# clock-matrix.net
KiCad netlist of a schematic drawn in EAGLE
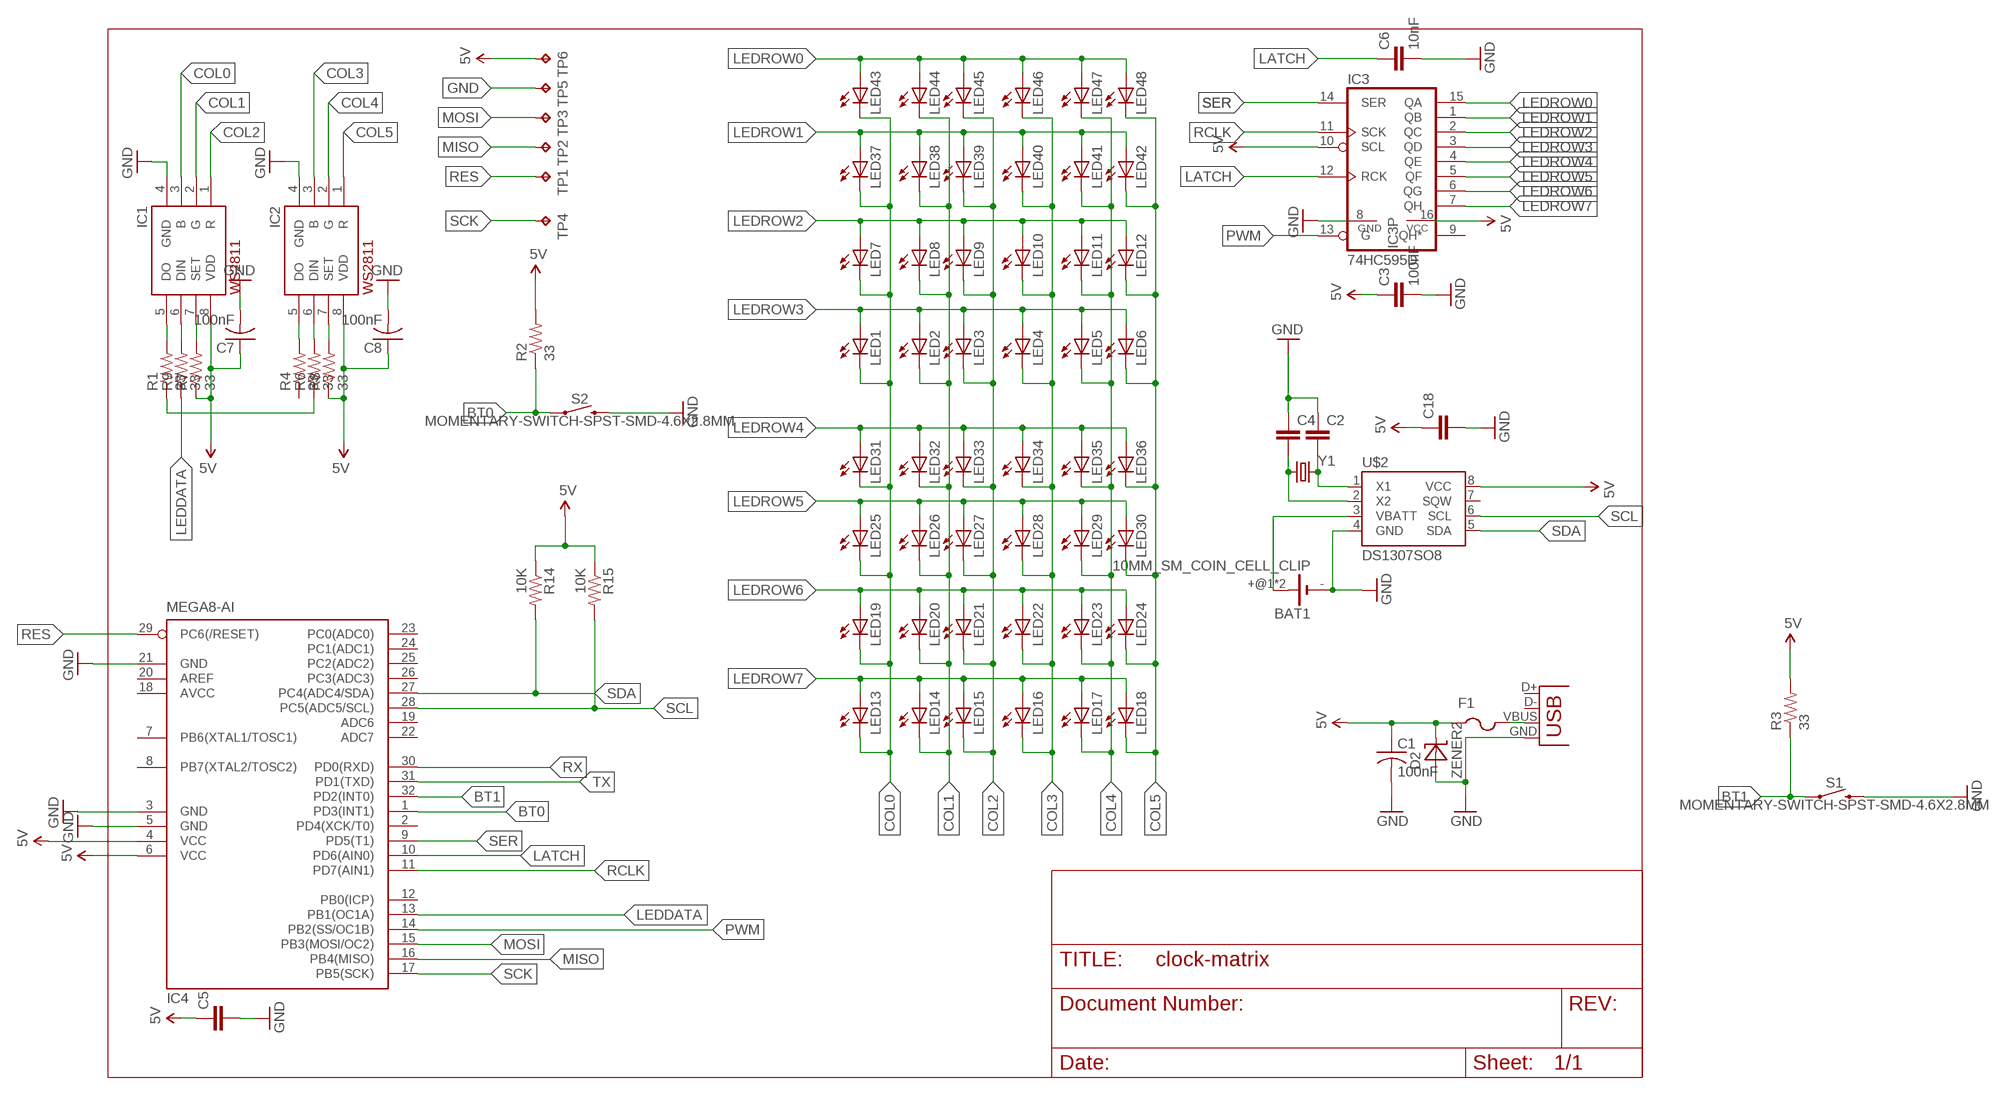
[diagram p0: schematic, sheet 1]

(export (version "E")
  (design (tool "Eeschema 10.0.6"))
  (components
    (comp (ref "BAT1")
      (value "10MM_SM_COIN_CELL_CLIP")
      (footprint "eagle-import:10MM_SM_COIN_CELL_CLIP")
      (libsource (lib "eagle-import") (part "10MM_SM_COIN_CELL_CLIP"))
    )
    (comp (ref "C1")
      (value "100nF")
      (footprint "eagle-import:C0603")
      (libsource (lib "eagle-import") (part "C-USC0603"))
    )
    (comp (ref "C2")
      (value "C-EUC0603")
      (footprint "eagle-import:C0603")
      (libsource (lib "eagle-import") (part "C-EUC0603"))
    )
    (comp (ref "C3")
      (value "100nF")
      (footprint "eagle-import:C0603")
      (libsource (lib "eagle-import") (part "C-EUC0603"))
    )
    (comp (ref "C4")
      (value "C-EUC0603")
      (footprint "eagle-import:C0603")
      (libsource (lib "eagle-import") (part "C-EUC0603"))
    )
    (comp (ref "C5")
      (value "C-EUC0603")
      (footprint "eagle-import:C0603")
      (libsource (lib "eagle-import") (part "C-EUC0603"))
    )
    (comp (ref "C6")
      (value "10nF")
      (footprint "eagle-import:C0603")
      (libsource (lib "eagle-import") (part "C-EUC0603"))
    )
    (comp (ref "C7")
      (value "100nF")
      (footprint "eagle-import:C0603")
      (libsource (lib "eagle-import") (part "C-USC0603"))
    )
    (comp (ref "C8")
      (value "100nF")
      (footprint "eagle-import:C0603")
      (libsource (lib "eagle-import") (part "C-USC0603"))
    )
    (comp (ref "C18")
      (value "C-EUC0603")
      (footprint "eagle-import:C0603")
      (libsource (lib "eagle-import") (part "C-EUC0603"))
    )
    (comp (ref "D2")
      (value "ZENER2")
      (footprint "eagle-import:SOD123")
      (libsource (lib "eagle-import") (part "ZENER2"))
    )
    (comp (ref "F1")
      (value "PTCFUSE-1206")
      (footprint "eagle-import:R1206")
      (libsource (lib "eagle-import") (part "PTCFUSE-1206"))
    )
    (comp (ref "IC1")
      (value "WS2811-SOP8")
      (footprint "eagle-import:SO08-SKINNYPADS")
      (libsource (lib "eagle-import") (part "WS2811-SOP8"))
    )
    (comp (ref "IC2")
      (value "WS2811-SOP8")
      (footprint "eagle-import:SO08-SKINNYPADS")
      (libsource (lib "eagle-import") (part "WS2811-SOP8"))
    )
    (comp (ref "IC3")
      (value "74HC595D")
      (footprint "eagle-import:SO16")
      (libsource (lib "eagle-import") (part "74595DHC"))
    )
    (comp (ref "IC4")
      (value "MEGA8-AI")
      (footprint "eagle-import:TQFP32-08")
      (fields (field (name "MPN") "ATMEGA8-16AU"))
      (libsource (lib "eagle-import") (part "MEGA8-AI"))
    )
    (comp (ref "LED1")
      (value "LED1206")
      (footprint "eagle-import:LED-1206")
      (libsource (lib "eagle-import") (part "LED1206"))
    )
    (comp (ref "LED2")
      (value "LED1206")
      (footprint "eagle-import:LED-1206")
      (libsource (lib "eagle-import") (part "LED1206"))
    )
    (comp (ref "LED3")
      (value "LED1206")
      (footprint "eagle-import:LED-1206")
      (libsource (lib "eagle-import") (part "LED1206"))
    )
    (comp (ref "LED4")
      (value "LED1206")
      (footprint "eagle-import:LED-1206")
      (libsource (lib "eagle-import") (part "LED1206"))
    )
    (comp (ref "LED5")
      (value "LED1206")
      (footprint "eagle-import:LED-1206")
      (libsource (lib "eagle-import") (part "LED1206"))
    )
    (comp (ref "LED6")
      (value "LED1206")
      (footprint "eagle-import:LED-1206")
      (libsource (lib "eagle-import") (part "LED1206"))
    )
    (comp (ref "LED7")
      (value "LED1206")
      (footprint "eagle-import:LED-1206")
      (libsource (lib "eagle-import") (part "LED1206"))
    )
    (comp (ref "LED8")
      (value "LED1206")
      (footprint "eagle-import:LED-1206")
      (libsource (lib "eagle-import") (part "LED1206"))
    )
    (comp (ref "LED9")
      (value "LED1206")
      (footprint "eagle-import:LED-1206")
      (libsource (lib "eagle-import") (part "LED1206"))
    )
    (comp (ref "LED10")
      (value "LED1206")
      (footprint "eagle-import:LED-1206")
      (libsource (lib "eagle-import") (part "LED1206"))
    )
    (comp (ref "LED11")
      (value "LED1206")
      (footprint "eagle-import:LED-1206")
      (libsource (lib "eagle-import") (part "LED1206"))
    )
    (comp (ref "LED12")
      (value "LED1206")
      (footprint "eagle-import:LED-1206")
      (libsource (lib "eagle-import") (part "LED1206"))
    )
    (comp (ref "LED13")
      (value "LED1206")
      (footprint "eagle-import:LED-1206")
      (libsource (lib "eagle-import") (part "LED1206"))
    )
    (comp (ref "LED14")
      (value "LED1206")
      (footprint "eagle-import:LED-1206")
      (libsource (lib "eagle-import") (part "LED1206"))
    )
    (comp (ref "LED15")
      (value "LED1206")
      (footprint "eagle-import:LED-1206")
      (libsource (lib "eagle-import") (part "LED1206"))
    )
    (comp (ref "LED16")
      (value "LED1206")
      (footprint "eagle-import:LED-1206")
      (libsource (lib "eagle-import") (part "LED1206"))
    )
    (comp (ref "LED17")
      (value "LED1206")
      (footprint "eagle-import:LED-1206")
      (libsource (lib "eagle-import") (part "LED1206"))
    )
    (comp (ref "LED18")
      (value "LED1206")
      (footprint "eagle-import:LED-1206")
      (libsource (lib "eagle-import") (part "LED1206"))
    )
    (comp (ref "LED19")
      (value "LED1206")
      (footprint "eagle-import:LED-1206")
      (libsource (lib "eagle-import") (part "LED1206"))
    )
    (comp (ref "LED20")
      (value "LED1206")
      (footprint "eagle-import:LED-1206")
      (libsource (lib "eagle-import") (part "LED1206"))
    )
    (comp (ref "LED21")
      (value "LED1206")
      (footprint "eagle-import:LED-1206")
      (libsource (lib "eagle-import") (part "LED1206"))
    )
    (comp (ref "LED22")
      (value "LED1206")
      (footprint "eagle-import:LED-1206")
      (libsource (lib "eagle-import") (part "LED1206"))
    )
    (comp (ref "LED23")
      (value "LED1206")
      (footprint "eagle-import:LED-1206")
      (libsource (lib "eagle-import") (part "LED1206"))
    )
    (comp (ref "LED24")
      (value "LED1206")
      (footprint "eagle-import:LED-1206")
      (libsource (lib "eagle-import") (part "LED1206"))
    )
    (comp (ref "LED25")
      (value "LED1206")
      (footprint "eagle-import:LED-1206")
      (libsource (lib "eagle-import") (part "LED1206"))
    )
    (comp (ref "LED26")
      (value "LED1206")
      (footprint "eagle-import:LED-1206")
      (libsource (lib "eagle-import") (part "LED1206"))
    )
    (comp (ref "LED27")
      (value "LED1206")
      (footprint "eagle-import:LED-1206")
      (libsource (lib "eagle-import") (part "LED1206"))
    )
    (comp (ref "LED28")
      (value "LED1206")
      (footprint "eagle-import:LED-1206")
      (libsource (lib "eagle-import") (part "LED1206"))
    )
    (comp (ref "LED29")
      (value "LED1206")
      (footprint "eagle-import:LED-1206")
      (libsource (lib "eagle-import") (part "LED1206"))
    )
    (comp (ref "LED30")
      (value "LED1206")
      (footprint "eagle-import:LED-1206")
      (libsource (lib "eagle-import") (part "LED1206"))
    )
    (comp (ref "LED31")
      (value "LED1206")
      (footprint "eagle-import:LED-1206")
      (libsource (lib "eagle-import") (part "LED1206"))
    )
    (comp (ref "LED32")
      (value "LED1206")
      (footprint "eagle-import:LED-1206")
      (libsource (lib "eagle-import") (part "LED1206"))
    )
    (comp (ref "LED33")
      (value "LED1206")
      (footprint "eagle-import:LED-1206")
      (libsource (lib "eagle-import") (part "LED1206"))
    )
    (comp (ref "LED34")
      (value "LED1206")
      (footprint "eagle-import:LED-1206")
      (libsource (lib "eagle-import") (part "LED1206"))
    )
    (comp (ref "LED35")
      (value "LED1206")
      (footprint "eagle-import:LED-1206")
      (libsource (lib "eagle-import") (part "LED1206"))
    )
    (comp (ref "LED36")
      (value "LED1206")
      (footprint "eagle-import:LED-1206")
      (libsource (lib "eagle-import") (part "LED1206"))
    )
    (comp (ref "LED37")
      (value "LED1206")
      (footprint "eagle-import:LED-1206")
      (libsource (lib "eagle-import") (part "LED1206"))
    )
    (comp (ref "LED38")
      (value "LED1206")
      (footprint "eagle-import:LED-1206")
      (libsource (lib "eagle-import") (part "LED1206"))
    )
    (comp (ref "LED39")
      (value "LED1206")
      (footprint "eagle-import:LED-1206")
      (libsource (lib "eagle-import") (part "LED1206"))
    )
    (comp (ref "LED40")
      (value "LED1206")
      (footprint "eagle-import:LED-1206")
      (libsource (lib "eagle-import") (part "LED1206"))
    )
    (comp (ref "LED41")
      (value "LED1206")
      (footprint "eagle-import:LED-1206")
      (libsource (lib "eagle-import") (part "LED1206"))
    )
    (comp (ref "LED42")
      (value "LED1206")
      (footprint "eagle-import:LED-1206")
      (libsource (lib "eagle-import") (part "LED1206"))
    )
    (comp (ref "LED43")
      (value "LED1206")
      (footprint "eagle-import:LED-1206")
      (libsource (lib "eagle-import") (part "LED1206"))
    )
    (comp (ref "LED44")
      (value "LED1206")
      (footprint "eagle-import:LED-1206")
      (libsource (lib "eagle-import") (part "LED1206"))
    )
    (comp (ref "LED45")
      (value "LED1206")
      (footprint "eagle-import:LED-1206")
      (libsource (lib "eagle-import") (part "LED1206"))
    )
    (comp (ref "LED46")
      (value "LED1206")
      (footprint "eagle-import:LED-1206")
      (libsource (lib "eagle-import") (part "LED1206"))
    )
    (comp (ref "LED47")
      (value "LED1206")
      (footprint "eagle-import:LED-1206")
      (libsource (lib "eagle-import") (part "LED1206"))
    )
    (comp (ref "LED48")
      (value "LED1206")
      (footprint "eagle-import:LED-1206")
      (libsource (lib "eagle-import") (part "LED1206"))
    )
    (comp (ref "R1")
      (value "33")
      (footprint "eagle-import:R0603")
      (libsource (lib "eagle-import") (part "R-US_R0603"))
    )
    (comp (ref "R2")
      (value "33")
      (footprint "eagle-import:R0603")
      (libsource (lib "eagle-import") (part "R-US_R0603"))
    )
    (comp (ref "R3")
      (value "33")
      (footprint "eagle-import:R0603")
      (libsource (lib "eagle-import") (part "R-US_R0603"))
    )
    (comp (ref "R4")
      (value "33")
      (footprint "eagle-import:R0603")
      (libsource (lib "eagle-import") (part "R-US_R0603"))
    )
    (comp (ref "R6")
      (value "33")
      (footprint "eagle-import:R0603")
      (libsource (lib "eagle-import") (part "R-US_R0603"))
    )
    (comp (ref "R7")
      (value "33")
      (footprint "eagle-import:R0603")
      (libsource (lib "eagle-import") (part "R-US_R0603"))
    )
    (comp (ref "R8")
      (value "33")
      (footprint "eagle-import:R0603")
      (libsource (lib "eagle-import") (part "R-US_R0603"))
    )
    (comp (ref "R9")
      (value "33")
      (footprint "eagle-import:R0603")
      (libsource (lib "eagle-import") (part "R-US_R0603"))
    )
    (comp (ref "R14")
      (value "10K")
      (footprint "eagle-import:R0603")
      (libsource (lib "eagle-import") (part "rcl_R-US_R0603"))
    )
    (comp (ref "R15")
      (value "10K")
      (footprint "eagle-import:R0603")
      (libsource (lib "eagle-import") (part "rcl_R-US_R0603"))
    )
    (comp (ref "S1")
      (value "MOMENTARY-SWITCH-SPST-SMD-4.6X2.8MM")
      (footprint "eagle-import:TACTILE_SWITCH_SMD_4.6X2.8MM")
      (libsource (lib "eagle-import") (part "MOMENTARY-SWITCH-SPST-SMD-4.6X2.8MM"))
    )
    (comp (ref "S2")
      (value "MOMENTARY-SWITCH-SPST-SMD-4.6X2.8MM")
      (footprint "eagle-import:TACTILE_SWITCH_SMD_4.6X2.8MM")
      (libsource (lib "eagle-import") (part "MOMENTARY-SWITCH-SPST-SMD-4.6X2.8MM"))
    )
    (comp (ref "TP1")
      (value "TPTP10R")
      (footprint "eagle-import:TP10R")
      (libsource (lib "eagle-import") (part "TPTP10R"))
    )
    (comp (ref "TP2")
      (value "TPTP10R")
      (footprint "eagle-import:TP10R")
      (libsource (lib "eagle-import") (part "TPTP10R"))
    )
    (comp (ref "TP3")
      (value "TPTP10R")
      (footprint "eagle-import:TP10R")
      (libsource (lib "eagle-import") (part "TPTP10R"))
    )
    (comp (ref "TP4")
      (value "TPTP10R")
      (footprint "eagle-import:TP10R")
      (libsource (lib "eagle-import") (part "TPTP10R"))
    )
    (comp (ref "TP5")
      (value "TPTP10R")
      (footprint "eagle-import:TP10R")
      (libsource (lib "eagle-import") (part "TPTP10R"))
    )
    (comp (ref "TP6")
      (value "TPTP10R")
      (footprint "eagle-import:TP10R")
      (libsource (lib "eagle-import") (part "TPTP10R"))
    )
    (comp (ref "U$2")
      (value "DS1307SO8")
      (footprint "eagle-import:SO08")
      (libsource (lib "eagle-import") (part "DS1307SO8"))
    )
    (comp (ref "X2")
      (value "USB-MICROB")
      (footprint "eagle-import:USB-MICROB")
      (libsource (lib "eagle-import") (part "USB-MICROB"))
    )
    (comp (ref "Y1")
      (value "CRYSTALTC26H")
      (footprint "eagle-import:TC26H")
      (libsource (lib "eagle-import") (part "CRYSTALTC26H"))
    )
  )
  (nets
    (net (code "1") (name "/AVCC") (class "Default")
      (node (ref "IC4") (pin "18") (pinfunction "AVCC_18") (pintype "power_in"))
    )
    (net (code "2") (name "5V") (class "Default")
      (node (ref "C1") (pin "1") (pinfunction "1_1") (pintype "passive"))
      (node (ref "C18") (pin "1") (pinfunction "1_1") (pintype "passive"))
      (node (ref "C3") (pin "1") (pinfunction "1_1") (pintype "passive"))
      (node (ref "C5") (pin "1") (pinfunction "1_1") (pintype "passive"))
      (node (ref "C7") (pin "1") (pinfunction "1_1") (pintype "passive"))
      (node (ref "C8") (pin "1") (pinfunction "1_1") (pintype "passive"))
      (node (ref "D2") (pin "C") (pinfunction "C_C") (pintype "passive"))
      (node (ref "F1") (pin "1") (pinfunction "1_1") (pintype "passive"))
      (node (ref "IC1") (pin "8") (pinfunction "VDD_8") (pintype "power_in"))
      (node (ref "IC2") (pin "8") (pinfunction "VDD_8") (pintype "power_in"))
      (node (ref "IC3") (pin "10") (pinfunction "SCL_10") (pintype "input"))
      (node (ref "IC3") (pin "16") (pinfunction "VCC_16") (pintype "power_in"))
      (node (ref "IC4") (pin "4") (pinfunction "VCC_4") (pintype "power_in"))
      (node (ref "IC4") (pin "6") (pinfunction "VCC_6") (pintype "power_in"))
      (node (ref "R14") (pin "1") (pinfunction "1_1") (pintype "passive"))
      (node (ref "R15") (pin "1") (pinfunction "1_1") (pintype "passive"))
      (node (ref "R2") (pin "2") (pinfunction "2_2") (pintype "passive"))
      (node (ref "R3") (pin "2") (pinfunction "2_2") (pintype "passive"))
      (node (ref "R7") (pin "1") (pinfunction "1_1") (pintype "passive"))
      (node (ref "R8") (pin "1") (pinfunction "1_1") (pintype "passive"))
      (node (ref "TP6") (pin "TP") (pinfunction "TP_TP") (pintype "input"))
      (node (ref "U$2") (pin "8") (pinfunction "VCC_8") (pintype "bidirectional"))
    )
    (net (code "3") (name "BT0") (class "Default")
      (node (ref "IC4") (pin "1") (pinfunction "PD3(INT1)_1") (pintype "bidirectional"))
      (node (ref "R2") (pin "1") (pinfunction "1_1") (pintype "passive"))
      (node (ref "S2") (pin "1") (pinfunction "1_1") (pintype "passive"))
      (node (ref "S2") (pin "2") (pinfunction "1_2") (pintype "passive"))
    )
    (net (code "4") (name "BT1") (class "Default")
      (node (ref "IC4") (pin "32") (pinfunction "PD2(INT0)_32") (pintype "bidirectional"))
      (node (ref "R3") (pin "1") (pinfunction "1_1") (pintype "passive"))
      (node (ref "S1") (pin "1") (pinfunction "1_1") (pintype "passive"))
      (node (ref "S1") (pin "2") (pinfunction "1_2") (pintype "passive"))
    )
    (net (code "5") (name "COL0") (class "Default")
      (node (ref "IC1") (pin "3") (pinfunction "B_3") (pintype "open_collector"))
      (node (ref "LED1") (pin "C") (pinfunction "C_C") (pintype "passive"))
      (node (ref "LED13") (pin "C") (pinfunction "C_C") (pintype "passive"))
      (node (ref "LED19") (pin "C") (pinfunction "C_C") (pintype "passive"))
      (node (ref "LED25") (pin "C") (pinfunction "C_C") (pintype "passive"))
      (node (ref "LED31") (pin "C") (pinfunction "C_C") (pintype "passive"))
      (node (ref "LED37") (pin "C") (pinfunction "C_C") (pintype "passive"))
      (node (ref "LED43") (pin "C") (pinfunction "C_C") (pintype "passive"))
      (node (ref "LED7") (pin "C") (pinfunction "C_C") (pintype "passive"))
    )
    (net (code "6") (name "COL1") (class "Default")
      (node (ref "IC1") (pin "2") (pinfunction "G_2") (pintype "open_collector"))
      (node (ref "LED14") (pin "C") (pinfunction "C_C") (pintype "passive"))
      (node (ref "LED2") (pin "C") (pinfunction "C_C") (pintype "passive"))
      (node (ref "LED20") (pin "C") (pinfunction "C_C") (pintype "passive"))
      (node (ref "LED26") (pin "C") (pinfunction "C_C") (pintype "passive"))
      (node (ref "LED32") (pin "C") (pinfunction "C_C") (pintype "passive"))
      (node (ref "LED38") (pin "C") (pinfunction "C_C") (pintype "passive"))
      (node (ref "LED44") (pin "C") (pinfunction "C_C") (pintype "passive"))
      (node (ref "LED8") (pin "C") (pinfunction "C_C") (pintype "passive"))
    )
    (net (code "7") (name "COL2") (class "Default")
      (node (ref "IC1") (pin "1") (pinfunction "R_1") (pintype "open_collector"))
      (node (ref "LED15") (pin "C") (pinfunction "C_C") (pintype "passive"))
      (node (ref "LED21") (pin "C") (pinfunction "C_C") (pintype "passive"))
      (node (ref "LED27") (pin "C") (pinfunction "C_C") (pintype "passive"))
      (node (ref "LED3") (pin "C") (pinfunction "C_C") (pintype "passive"))
      (node (ref "LED33") (pin "C") (pinfunction "C_C") (pintype "passive"))
      (node (ref "LED39") (pin "C") (pinfunction "C_C") (pintype "passive"))
      (node (ref "LED45") (pin "C") (pinfunction "C_C") (pintype "passive"))
      (node (ref "LED9") (pin "C") (pinfunction "C_C") (pintype "passive"))
    )
    (net (code "8") (name "COL3") (class "Default")
      (node (ref "IC2") (pin "3") (pinfunction "B_3") (pintype "open_collector"))
      (node (ref "LED10") (pin "C") (pinfunction "C_C") (pintype "passive"))
      (node (ref "LED16") (pin "C") (pinfunction "C_C") (pintype "passive"))
      (node (ref "LED22") (pin "C") (pinfunction "C_C") (pintype "passive"))
      (node (ref "LED28") (pin "C") (pinfunction "C_C") (pintype "passive"))
      (node (ref "LED34") (pin "C") (pinfunction "C_C") (pintype "passive"))
      (node (ref "LED4") (pin "C") (pinfunction "C_C") (pintype "passive"))
      (node (ref "LED40") (pin "C") (pinfunction "C_C") (pintype "passive"))
      (node (ref "LED46") (pin "C") (pinfunction "C_C") (pintype "passive"))
    )
    (net (code "9") (name "COL4") (class "Default")
      (node (ref "IC2") (pin "2") (pinfunction "G_2") (pintype "open_collector"))
      (node (ref "LED11") (pin "C") (pinfunction "C_C") (pintype "passive"))
      (node (ref "LED17") (pin "C") (pinfunction "C_C") (pintype "passive"))
      (node (ref "LED23") (pin "C") (pinfunction "C_C") (pintype "passive"))
      (node (ref "LED29") (pin "C") (pinfunction "C_C") (pintype "passive"))
      (node (ref "LED35") (pin "C") (pinfunction "C_C") (pintype "passive"))
      (node (ref "LED41") (pin "C") (pinfunction "C_C") (pintype "passive"))
      (node (ref "LED47") (pin "C") (pinfunction "C_C") (pintype "passive"))
      (node (ref "LED5") (pin "C") (pinfunction "C_C") (pintype "passive"))
    )
    (net (code "10") (name "COL5") (class "Default")
      (node (ref "IC2") (pin "1") (pinfunction "R_1") (pintype "open_collector"))
      (node (ref "LED12") (pin "C") (pinfunction "C_C") (pintype "passive"))
      (node (ref "LED18") (pin "C") (pinfunction "C_C") (pintype "passive"))
      (node (ref "LED24") (pin "C") (pinfunction "C_C") (pintype "passive"))
      (node (ref "LED30") (pin "C") (pinfunction "C_C") (pintype "passive"))
      (node (ref "LED36") (pin "C") (pinfunction "C_C") (pintype "passive"))
      (node (ref "LED42") (pin "C") (pinfunction "C_C") (pintype "passive"))
      (node (ref "LED48") (pin "C") (pinfunction "C_C") (pintype "passive"))
      (node (ref "LED6") (pin "C") (pinfunction "C_C") (pintype "passive"))
    )
    (net (code "11") (name "GND") (class "Default")
      (node (ref "BAT1") (pin "-") (pinfunction "-_-") (pintype "passive"))
      (node (ref "C1") (pin "2") (pinfunction "2_2") (pintype "passive"))
      (node (ref "C18") (pin "2") (pinfunction "2_2") (pintype "passive"))
      (node (ref "C2") (pin "1") (pinfunction "1_1") (pintype "passive"))
      (node (ref "C3") (pin "2") (pinfunction "2_2") (pintype "passive"))
      (node (ref "C4") (pin "1") (pinfunction "1_1") (pintype "passive"))
      (node (ref "C5") (pin "2") (pinfunction "2_2") (pintype "passive"))
      (node (ref "C6") (pin "2") (pinfunction "2_2") (pintype "passive"))
      (node (ref "C7") (pin "2") (pinfunction "2_2") (pintype "passive"))
      (node (ref "C8") (pin "2") (pinfunction "2_2") (pintype "passive"))
      (node (ref "D2") (pin "A") (pinfunction "A_A") (pintype "passive"))
      (node (ref "IC1") (pin "4") (pinfunction "GND_4") (pintype "power_in"))
      (node (ref "IC2") (pin "4") (pinfunction "GND_4") (pintype "power_in"))
      (node (ref "IC3") (pin "8") (pinfunction "GND_8") (pintype "power_in"))
      (node (ref "IC4") (pin "21") (pinfunction "GND_21") (pintype "power_in"))
      (node (ref "IC4") (pin "3") (pinfunction "GND_3") (pintype "power_in"))
      (node (ref "IC4") (pin "5") (pinfunction "GND_5") (pintype "power_in"))
      (node (ref "S1") (pin "3") (pinfunction "2_3") (pintype "passive"))
      (node (ref "S1") (pin "4") (pinfunction "2_4") (pintype "passive"))
      (node (ref "S2") (pin "3") (pinfunction "2_3") (pintype "passive"))
      (node (ref "S2") (pin "4") (pinfunction "2_4") (pintype "passive"))
      (node (ref "TP5") (pin "TP") (pinfunction "TP_TP") (pintype "input"))
      (node (ref "U$2") (pin "4") (pinfunction "GND_4") (pintype "bidirectional"))
      (node (ref "X2") (pin "GND") (pinfunction "GND_GND") (pintype "bidirectional"))
    )
    (net (code "12") (name "LATCH") (class "Default")
      (node (ref "C6") (pin "1") (pinfunction "1_1") (pintype "passive"))
      (node (ref "IC3") (pin "12") (pinfunction "RCK_12") (pintype "input"))
      (node (ref "IC4") (pin "10") (pinfunction "PD6(AIN0)_10") (pintype "bidirectional"))
    )
    (net (code "13") (name "LEDDATA") (class "Default")
      (node (ref "IC4") (pin "13") (pinfunction "PB1(OC1A)_13") (pintype "bidirectional"))
      (node (ref "R9") (pin "1") (pinfunction "1_1") (pintype "passive"))
    )
    (net (code "14") (name "LEDROW0") (class "Default")
      (node (ref "IC3") (pin "15") (pinfunction "QA_15") (pintype "tri_state"))
      (node (ref "LED43") (pin "A") (pinfunction "A_A") (pintype "passive"))
      (node (ref "LED44") (pin "A") (pinfunction "A_A") (pintype "passive"))
      (node (ref "LED45") (pin "A") (pinfunction "A_A") (pintype "passive"))
      (node (ref "LED46") (pin "A") (pinfunction "A_A") (pintype "passive"))
      (node (ref "LED47") (pin "A") (pinfunction "A_A") (pintype "passive"))
      (node (ref "LED48") (pin "A") (pinfunction "A_A") (pintype "passive"))
    )
    (net (code "15") (name "LEDROW1") (class "Default")
      (node (ref "IC3") (pin "1") (pinfunction "QB_1") (pintype "tri_state"))
      (node (ref "LED37") (pin "A") (pinfunction "A_A") (pintype "passive"))
      (node (ref "LED38") (pin "A") (pinfunction "A_A") (pintype "passive"))
      (node (ref "LED39") (pin "A") (pinfunction "A_A") (pintype "passive"))
      (node (ref "LED40") (pin "A") (pinfunction "A_A") (pintype "passive"))
      (node (ref "LED41") (pin "A") (pinfunction "A_A") (pintype "passive"))
      (node (ref "LED42") (pin "A") (pinfunction "A_A") (pintype "passive"))
    )
    (net (code "16") (name "LEDROW2") (class "Default")
      (node (ref "IC3") (pin "2") (pinfunction "QC_2") (pintype "tri_state"))
      (node (ref "LED10") (pin "A") (pinfunction "A_A") (pintype "passive"))
      (node (ref "LED11") (pin "A") (pinfunction "A_A") (pintype "passive"))
      (node (ref "LED12") (pin "A") (pinfunction "A_A") (pintype "passive"))
      (node (ref "LED7") (pin "A") (pinfunction "A_A") (pintype "passive"))
      (node (ref "LED8") (pin "A") (pinfunction "A_A") (pintype "passive"))
      (node (ref "LED9") (pin "A") (pinfunction "A_A") (pintype "passive"))
    )
    (net (code "17") (name "LEDROW3") (class "Default")
      (node (ref "IC3") (pin "3") (pinfunction "QD_3") (pintype "tri_state"))
      (node (ref "LED1") (pin "A") (pinfunction "A_A") (pintype "passive"))
      (node (ref "LED2") (pin "A") (pinfunction "A_A") (pintype "passive"))
      (node (ref "LED3") (pin "A") (pinfunction "A_A") (pintype "passive"))
      (node (ref "LED4") (pin "A") (pinfunction "A_A") (pintype "passive"))
      (node (ref "LED5") (pin "A") (pinfunction "A_A") (pintype "passive"))
      (node (ref "LED6") (pin "A") (pinfunction "A_A") (pintype "passive"))
    )
    (net (code "18") (name "LEDROW4") (class "Default")
      (node (ref "IC3") (pin "4") (pinfunction "QE_4") (pintype "tri_state"))
      (node (ref "LED31") (pin "A") (pinfunction "A_A") (pintype "passive"))
      (node (ref "LED32") (pin "A") (pinfunction "A_A") (pintype "passive"))
      (node (ref "LED33") (pin "A") (pinfunction "A_A") (pintype "passive"))
      (node (ref "LED34") (pin "A") (pinfunction "A_A") (pintype "passive"))
      (node (ref "LED35") (pin "A") (pinfunction "A_A") (pintype "passive"))
      (node (ref "LED36") (pin "A") (pinfunction "A_A") (pintype "passive"))
    )
    (net (code "19") (name "LEDROW5") (class "Default")
      (node (ref "IC3") (pin "5") (pinfunction "QF_5") (pintype "tri_state"))
      (node (ref "LED25") (pin "A") (pinfunction "A_A") (pintype "passive"))
      (node (ref "LED26") (pin "A") (pinfunction "A_A") (pintype "passive"))
      (node (ref "LED27") (pin "A") (pinfunction "A_A") (pintype "passive"))
      (node (ref "LED28") (pin "A") (pinfunction "A_A") (pintype "passive"))
      (node (ref "LED29") (pin "A") (pinfunction "A_A") (pintype "passive"))
      (node (ref "LED30") (pin "A") (pinfunction "A_A") (pintype "passive"))
    )
    (net (code "20") (name "LEDROW6") (class "Default")
      (node (ref "IC3") (pin "6") (pinfunction "QG_6") (pintype "tri_state"))
      (node (ref "LED19") (pin "A") (pinfunction "A_A") (pintype "passive"))
      (node (ref "LED20") (pin "A") (pinfunction "A_A") (pintype "passive"))
      (node (ref "LED21") (pin "A") (pinfunction "A_A") (pintype "passive"))
      (node (ref "LED22") (pin "A") (pinfunction "A_A") (pintype "passive"))
      (node (ref "LED23") (pin "A") (pinfunction "A_A") (pintype "passive"))
      (node (ref "LED24") (pin "A") (pinfunction "A_A") (pintype "passive"))
    )
    (net (code "21") (name "LEDROW7") (class "Default")
      (node (ref "IC3") (pin "7") (pinfunction "QH_7") (pintype "tri_state"))
      (node (ref "LED13") (pin "A") (pinfunction "A_A") (pintype "passive"))
      (node (ref "LED14") (pin "A") (pinfunction "A_A") (pintype "passive"))
      (node (ref "LED15") (pin "A") (pinfunction "A_A") (pintype "passive"))
      (node (ref "LED16") (pin "A") (pinfunction "A_A") (pintype "passive"))
      (node (ref "LED17") (pin "A") (pinfunction "A_A") (pintype "passive"))
      (node (ref "LED18") (pin "A") (pinfunction "A_A") (pintype "passive"))
    )
    (net (code "22") (name "MISO") (class "Default")
      (node (ref "IC4") (pin "16") (pinfunction "PB4(MISO)_16") (pintype "bidirectional"))
      (node (ref "TP2") (pin "TP") (pinfunction "TP_TP") (pintype "input"))
    )
    (net (code "23") (name "MOSI") (class "Default")
      (node (ref "IC4") (pin "15") (pinfunction "PB3(MOSI/OC2)_15") (pintype "bidirectional"))
      (node (ref "TP3") (pin "TP") (pinfunction "TP_TP") (pintype "input"))
    )
    (net (code "24") (name "Net-(F1-Pad2)") (class "Default")
      (node (ref "F1") (pin "2") (pinfunction "2_2") (pintype "passive"))
      (node (ref "X2") (pin "VBUS") (pinfunction "VBUS_VBUS") (pintype "bidirectional"))
    )
    (net (code "25") (name "Net-(IC1-DIN)") (class "Default")
      (node (ref "IC1") (pin "6") (pinfunction "DIN_6") (pintype "input"))
      (node (ref "R9") (pin "2") (pinfunction "2_2") (pintype "passive"))
    )
    (net (code "26") (name "Net-(IC1-DO)") (class "Default")
      (node (ref "IC1") (pin "5") (pinfunction "DO_5") (pintype "output"))
      (node (ref "R1") (pin "2") (pinfunction "2_2") (pintype "passive"))
    )
    (net (code "27") (name "Net-(IC1-SET)") (class "Default")
      (node (ref "IC1") (pin "7") (pinfunction "SET_7") (pintype "input"))
      (node (ref "R7") (pin "2") (pinfunction "2_2") (pintype "passive"))
    )
    (net (code "28") (name "Net-(IC2-DIN)") (class "Default")
      (node (ref "IC2") (pin "6") (pinfunction "DIN_6") (pintype "input"))
      (node (ref "R6") (pin "2") (pinfunction "2_2") (pintype "passive"))
    )
    (net (code "29") (name "Net-(IC2-DO)") (class "Default")
      (node (ref "IC2") (pin "5") (pinfunction "DO_5") (pintype "output"))
      (node (ref "R4") (pin "2") (pinfunction "2_2") (pintype "passive"))
    )
    (net (code "30") (name "Net-(IC2-SET)") (class "Default")
      (node (ref "IC2") (pin "7") (pinfunction "SET_7") (pintype "input"))
      (node (ref "R8") (pin "2") (pinfunction "2_2") (pintype "passive"))
    )
    (net (code "31") (name "Net-(R1-Pad1)") (class "Default")
      (node (ref "R1") (pin "1") (pinfunction "1_1") (pintype "passive"))
      (node (ref "R6") (pin "1") (pinfunction "1_1") (pintype "passive"))
    )
    (net (code "32") (name "Net-(U$2-VBATT)") (class "Default")
      (node (ref "BAT1") (pin "+@1") (pinfunction "+_+@1") (pintype "passive"))
      (node (ref "BAT1") (pin "+@2") (pinfunction "+_+@2") (pintype "passive"))
      (node (ref "U$2") (pin "3") (pinfunction "VBATT_3") (pintype "bidirectional"))
    )
    (net (code "33") (name "Net-(U$2-X1)") (class "Default")
      (node (ref "C2") (pin "2") (pinfunction "2_2") (pintype "passive"))
      (node (ref "U$2") (pin "1") (pinfunction "X1_1") (pintype "bidirectional"))
      (node (ref "Y1") (pin "2") (pinfunction "2_2") (pintype "passive"))
    )
    (net (code "34") (name "Net-(U$2-X2)") (class "Default")
      (node (ref "C4") (pin "2") (pinfunction "2_2") (pintype "passive"))
      (node (ref "U$2") (pin "2") (pinfunction "X2_2") (pintype "bidirectional"))
      (node (ref "Y1") (pin "1") (pinfunction "1_1") (pintype "passive"))
    )
    (net (code "35") (name "PWM") (class "Default")
      (node (ref "IC3") (pin "13") (pinfunction "G_13") (pintype "input"))
      (node (ref "IC4") (pin "14") (pinfunction "PB2(SS/OC1B)_14") (pintype "bidirectional"))
    )
    (net (code "36") (name "RCLK") (class "Default")
      (node (ref "IC3") (pin "11") (pinfunction "SCK_11") (pintype "input"))
      (node (ref "IC4") (pin "11") (pinfunction "PD7(AIN1)_11") (pintype "bidirectional"))
    )
    (net (code "37") (name "RES") (class "Default")
      (node (ref "IC4") (pin "29") (pinfunction "PC6(/RESET)_29") (pintype "bidirectional"))
      (node (ref "TP1") (pin "TP") (pinfunction "TP_TP") (pintype "input"))
    )
    (net (code "38") (name "RX") (class "Default")
      (node (ref "IC4") (pin "30") (pinfunction "PD0(RXD)_30") (pintype "bidirectional"))
    )
    (net (code "39") (name "SCK") (class "Default")
      (node (ref "IC4") (pin "17") (pinfunction "PB5(SCK)_17") (pintype "bidirectional"))
      (node (ref "TP4") (pin "TP") (pinfunction "TP_TP") (pintype "input"))
    )
    (net (code "40") (name "SCL") (class "Default")
      (node (ref "IC4") (pin "28") (pinfunction "PC5(ADC5/SCL)_28") (pintype "bidirectional"))
      (node (ref "R15") (pin "2") (pinfunction "2_2") (pintype "passive"))
      (node (ref "U$2") (pin "6") (pinfunction "SCL_6") (pintype "bidirectional"))
    )
    (net (code "41") (name "SDA") (class "Default")
      (node (ref "IC4") (pin "27") (pinfunction "PC4(ADC4/SDA)_27") (pintype "bidirectional"))
      (node (ref "R14") (pin "2") (pinfunction "2_2") (pintype "passive"))
      (node (ref "U$2") (pin "5") (pinfunction "SDA_5") (pintype "bidirectional"))
    )
    (net (code "42") (name "SER") (class "Default")
      (node (ref "IC3") (pin "14") (pinfunction "SER_14") (pintype "input"))
      (node (ref "IC4") (pin "9") (pinfunction "PD5(T1)_9") (pintype "bidirectional"))
    )
    (net (code "43") (name "TX") (class "Default")
      (node (ref "IC4") (pin "31") (pinfunction "PD1(TXD)_31") (pintype "bidirectional"))
    )
    (net (code "44") (name "unconnected-(IC3A-QH*-Pad9)") (class "Default")
      (node (ref "IC3") (pin "9") (pinfunction "QH*_9") (pintype "tri_state"))
    )
    (net (code "45") (name "unconnected-(IC4-ADC6-Pad19)") (class "Default")
      (node (ref "IC4") (pin "19") (pinfunction "ADC6_19") (pintype "bidirectional"))
    )
    (net (code "46") (name "unconnected-(IC4-ADC7-Pad22)") (class "Default")
      (node (ref "IC4") (pin "22") (pinfunction "ADC7_22") (pintype "bidirectional"))
    )
    (net (code "47") (name "unconnected-(IC4-AREF-Pad20)") (class "Default")
      (node (ref "IC4") (pin "20") (pinfunction "AREF_20") (pintype "passive"))
    )
    (net (code "48") (name "unconnected-(IC4-PB0(ICP)-Pad12)") (class "Default")
      (node (ref "IC4") (pin "12") (pinfunction "PB0(ICP)_12") (pintype "bidirectional"))
    )
    (net (code "49") (name "unconnected-(IC4-PB6(XTAL1{slash}TOSC1)-Pad7)") (class "Default")
      (node (ref "IC4") (pin "7") (pinfunction "PB6(XTAL1/TOSC1)_7") (pintype "bidirectional"))
    )
    (net (code "50") (name "unconnected-(IC4-PB7(XTAL2{slash}TOSC2)-Pad8)") (class "Default")
      (node (ref "IC4") (pin "8") (pinfunction "PB7(XTAL2/TOSC2)_8") (pintype "bidirectional"))
    )
    (net (code "51") (name "unconnected-(IC4-PC0(ADC0)-Pad23)") (class "Default")
      (node (ref "IC4") (pin "23") (pinfunction "PC0(ADC0)_23") (pintype "bidirectional"))
    )
    (net (code "52") (name "unconnected-(IC4-PC1(ADC1)-Pad24)") (class "Default")
      (node (ref "IC4") (pin "24") (pinfunction "PC1(ADC1)_24") (pintype "bidirectional"))
    )
    (net (code "53") (name "unconnected-(IC4-PC2(ADC2)-Pad25)") (class "Default")
      (node (ref "IC4") (pin "25") (pinfunction "PC2(ADC2)_25") (pintype "bidirectional"))
    )
    (net (code "54") (name "unconnected-(IC4-PC3(ADC3)-Pad26)") (class "Default")
      (node (ref "IC4") (pin "26") (pinfunction "PC3(ADC3)_26") (pintype "bidirectional"))
    )
    (net (code "55") (name "unconnected-(IC4-PD4(XCK{slash}T0)-Pad2)") (class "Default")
      (node (ref "IC4") (pin "2") (pinfunction "PD4(XCK/T0)_2") (pintype "bidirectional"))
    )
    (net (code "56") (name "unconnected-(R4-Pad1)") (class "Default")
      (node (ref "R4") (pin "1") (pinfunction "1_1") (pintype "passive"))
    )
    (net (code "57") (name "unconnected-(U$2-SQW-Pad7)") (class "Default")
      (node (ref "U$2") (pin "7") (pinfunction "SQW_7") (pintype "bidirectional"))
    )
    (net (code "58") (name "unconnected-(X2-PadD+)") (class "Default")
      (node (ref "X2") (pin "D+") (pinfunction "D+_D+") (pintype "bidirectional"))
    )
    (net (code "59") (name "unconnected-(X2-PadD-)") (class "Default")
      (node (ref "X2") (pin "D-") (pinfunction "D-_D-") (pintype "bidirectional"))
    )
  )
)
